# toiletino.net
KiCad netlist of a schematic drawn in EAGLE
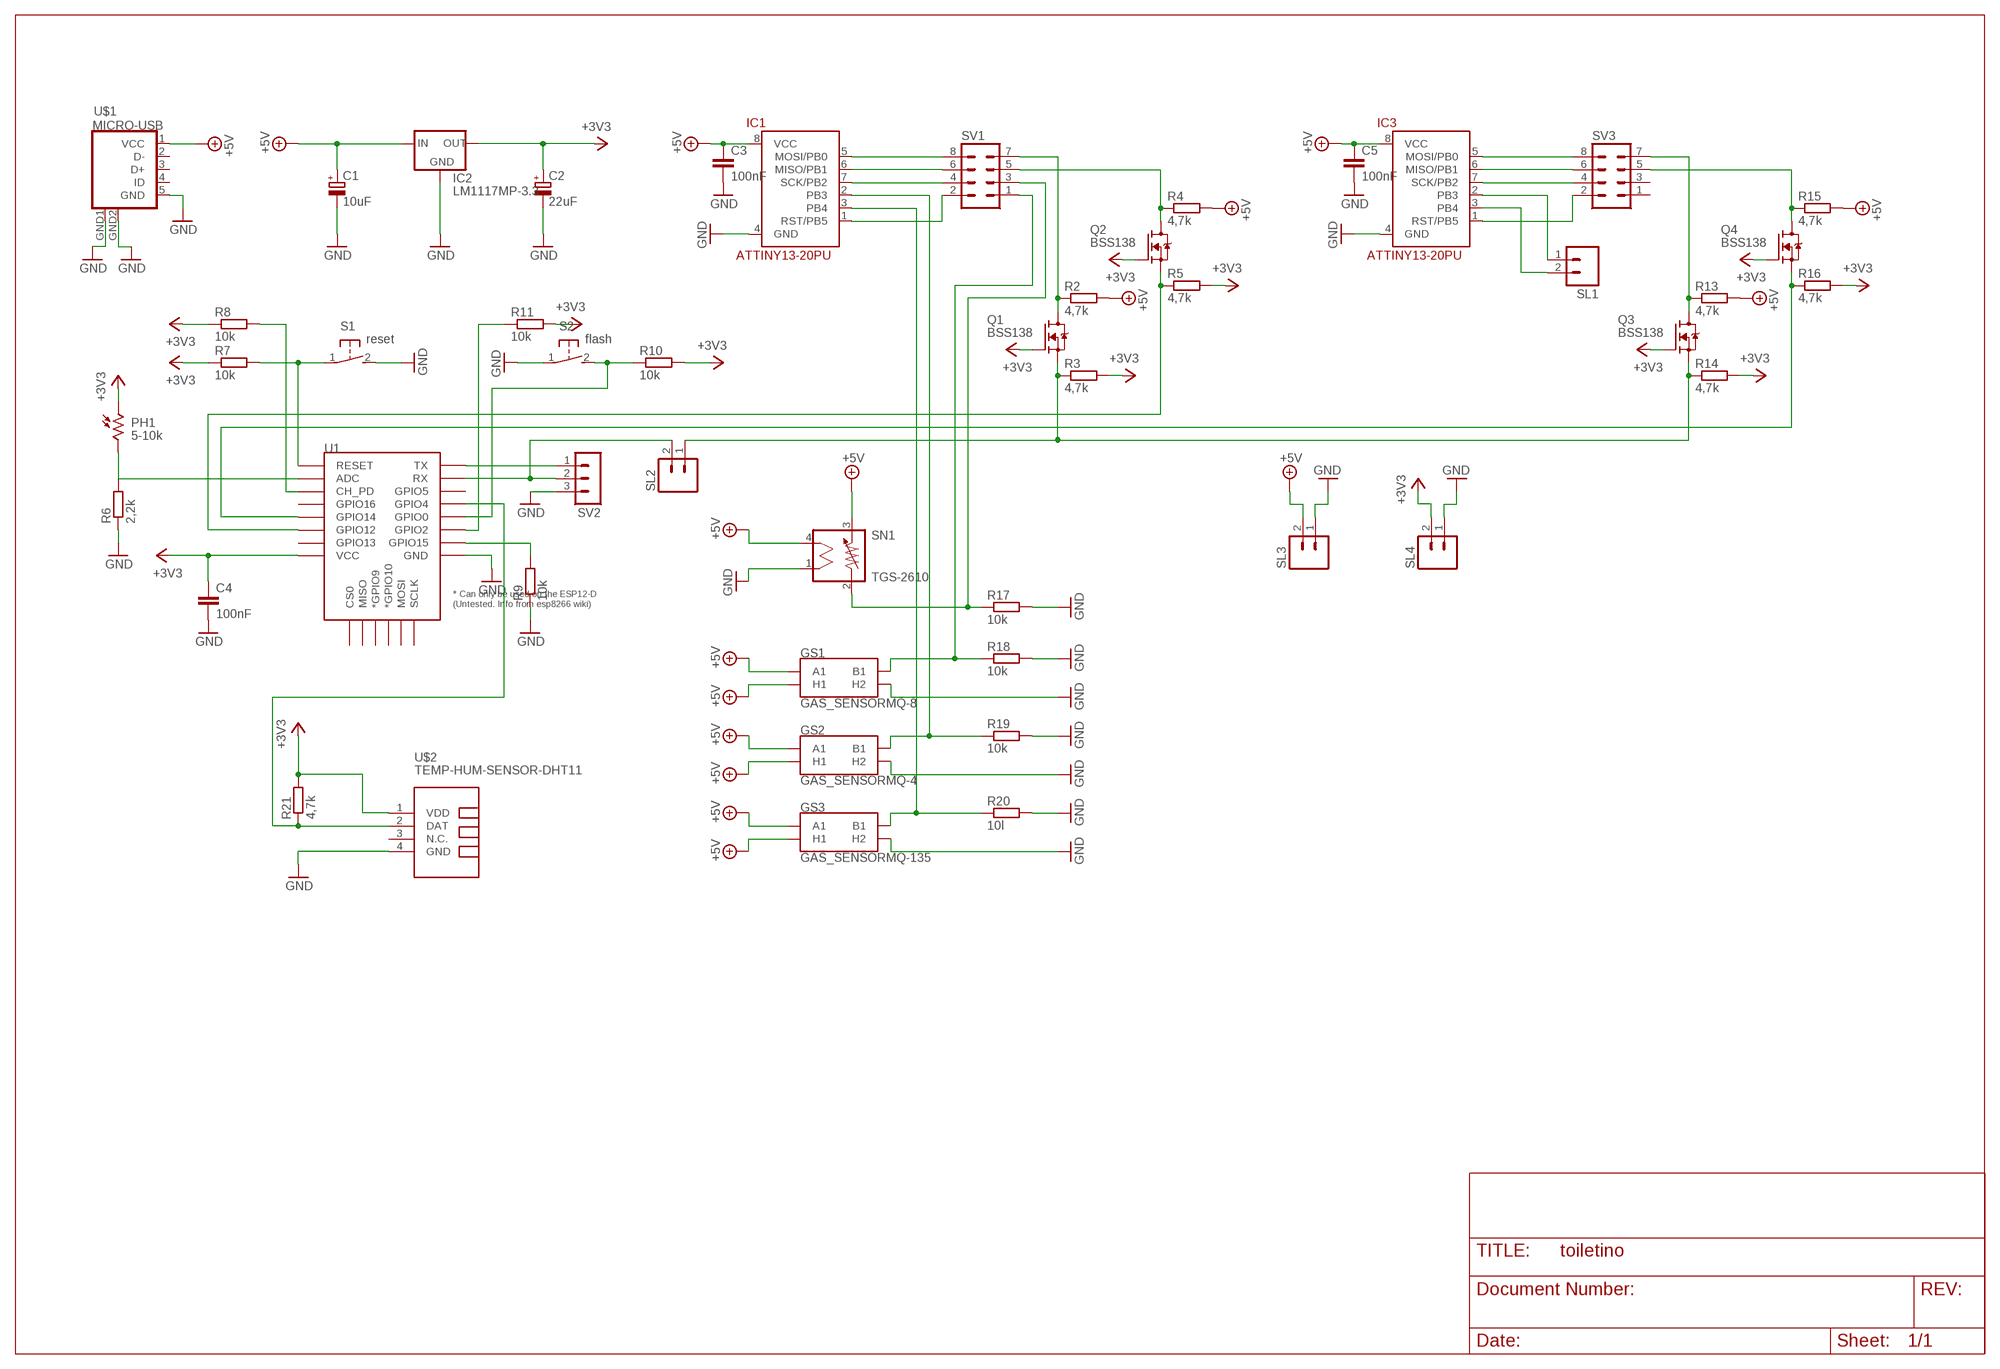
[diagram p0: schematic, sheet 1]

(export (version "E")
  (design (tool "Eeschema 10.0.6"))
  (components
    (comp (ref "C1")
      (value "10uF")
      (footprint "eagle-import:E2,5-6")
      (libsource (lib "eagle-import") (part "CPOL-EUE2.5-6"))
    )
    (comp (ref "C2")
      (value "22uF")
      (footprint "eagle-import:E2,5-6")
      (libsource (lib "eagle-import") (part "CPOL-EUE2.5-6"))
    )
    (comp (ref "C3")
      (value "100nF")
      (footprint "eagle-import:C025-025X050")
      (libsource (lib "eagle-import") (part "C-EU025-025X050"))
    )
    (comp (ref "C4")
      (value "100nF")
      (footprint "eagle-import:C025-025X050")
      (libsource (lib "eagle-import") (part "C-EU025-025X050"))
    )
    (comp (ref "C5")
      (value "100nF")
      (footprint "eagle-import:C025-025X050")
      (libsource (lib "eagle-import") (part "C-EU025-025X050"))
    )
    (comp (ref "GS1")
      (value "GAS_SENSORMQ-8")
      (footprint "eagle-import:GAS_SENSOR")
      (libsource (lib "eagle-import") (part "GAS_SENSORMQ-8"))
    )
    (comp (ref "GS2")
      (value "GAS_SENSORMQ-4")
      (footprint "eagle-import:GAS_SENSOR")
      (libsource (lib "eagle-import") (part "GAS_SENSORMQ-4"))
    )
    (comp (ref "GS3")
      (value "GAS_SENSORMQ-135")
      (footprint "eagle-import:GAS_SENSOR")
      (libsource (lib "eagle-import") (part "GAS_SENSORMQ-3"))
    )
    (comp (ref "IC1")
      (value "ATTINY13-20PU")
      (footprint "eagle-import:DIL08")
      (libsource (lib "eagle-import") (part "ATTINY13-20PU"))
    )
    (comp (ref "IC2")
      (value "LM1117MP-3.3")
      (footprint "eagle-import:SOT223")
      (fields (field (name "MF") "Texas Instruments"))
      (libsource (lib "eagle-import") (part "LM1117?-MP3.3"))
    )
    (comp (ref "IC3")
      (value "ATTINY13-20PU")
      (footprint "eagle-import:DIL08")
      (libsource (lib "eagle-import") (part "ATTINY13-20PU"))
    )
    (comp (ref "PH1")
      (value "5-10k")
      (footprint "eagle-import:TO-5_V10")
      (libsource (lib "eagle-import") (part "?1060V_21"))
    )
    (comp (ref "Q1")
      (value "BSS138")
      (footprint "eagle-import:SOT23")
      (fields (field (name "MF") "Fairchild"))
      (libsource (lib "eagle-import") (part "BSS138"))
    )
    (comp (ref "Q2")
      (value "BSS138")
      (footprint "eagle-import:SOT23")
      (fields (field (name "MF") "Fairchild"))
      (libsource (lib "eagle-import") (part "BSS138"))
    )
    (comp (ref "Q3")
      (value "BSS138")
      (footprint "eagle-import:SOT23")
      (fields (field (name "MF") "Fairchild"))
      (libsource (lib "eagle-import") (part "BSS138"))
    )
    (comp (ref "Q4")
      (value "BSS138")
      (footprint "eagle-import:SOT23")
      (fields (field (name "MF") "Fairchild"))
      (libsource (lib "eagle-import") (part "BSS138"))
    )
    (comp (ref "R2")
      (value "4,7k")
      (footprint "eagle-import:0207_10")
      (libsource (lib "eagle-import") (part "R-EU_0207/10"))
    )
    (comp (ref "R3")
      (value "4,7k")
      (footprint "eagle-import:0207_10")
      (libsource (lib "eagle-import") (part "R-EU_0207/10"))
    )
    (comp (ref "R4")
      (value "4,7k")
      (footprint "eagle-import:0207_10")
      (libsource (lib "eagle-import") (part "R-EU_0207/10"))
    )
    (comp (ref "R5")
      (value "4,7k")
      (footprint "eagle-import:0207_10")
      (libsource (lib "eagle-import") (part "R-EU_0207/10"))
    )
    (comp (ref "R6")
      (value "2,2k")
      (footprint "eagle-import:0207_10")
      (libsource (lib "eagle-import") (part "R-EU_0207/10"))
    )
    (comp (ref "R7")
      (value "10k")
      (footprint "eagle-import:0207_10")
      (libsource (lib "eagle-import") (part "R-EU_0207/10"))
    )
    (comp (ref "R8")
      (value "10k")
      (footprint "eagle-import:0207_10")
      (libsource (lib "eagle-import") (part "R-EU_0207/10"))
    )
    (comp (ref "R9")
      (value "10k")
      (footprint "eagle-import:0207_10")
      (libsource (lib "eagle-import") (part "R-EU_0207/10"))
    )
    (comp (ref "R10")
      (value "10k")
      (footprint "eagle-import:0207_10")
      (libsource (lib "eagle-import") (part "R-EU_0207/10"))
    )
    (comp (ref "R11")
      (value "10k")
      (footprint "eagle-import:0207_10")
      (libsource (lib "eagle-import") (part "R-EU_0207/10"))
    )
    (comp (ref "R13")
      (value "4,7k")
      (footprint "eagle-import:0207_10")
      (libsource (lib "eagle-import") (part "R-EU_0207/10"))
    )
    (comp (ref "R14")
      (value "4,7k")
      (footprint "eagle-import:0207_10")
      (libsource (lib "eagle-import") (part "R-EU_0207/10"))
    )
    (comp (ref "R15")
      (value "4,7k")
      (footprint "eagle-import:0207_10")
      (libsource (lib "eagle-import") (part "R-EU_0207/10"))
    )
    (comp (ref "R16")
      (value "4,7k")
      (footprint "eagle-import:0207_10")
      (libsource (lib "eagle-import") (part "R-EU_0207/10"))
    )
    (comp (ref "R17")
      (value "10k")
      (footprint "eagle-import:0207_10")
      (libsource (lib "eagle-import") (part "R-EU_0207/10"))
    )
    (comp (ref "R18")
      (value "10k")
      (footprint "eagle-import:0207_10")
      (libsource (lib "eagle-import") (part "R-EU_0207/10"))
    )
    (comp (ref "R19")
      (value "10k")
      (footprint "eagle-import:0207_10")
      (libsource (lib "eagle-import") (part "R-EU_0207/10"))
    )
    (comp (ref "R20")
      (value "10l")
      (footprint "eagle-import:0207_10")
      (libsource (lib "eagle-import") (part "R-EU_0207/10"))
    )
    (comp (ref "R21")
      (value "4,7k")
      (footprint "eagle-import:0207_10")
      (libsource (lib "eagle-import") (part "R-EU_0207/10"))
    )
    (comp (ref "S1")
      (value "reset")
      (footprint "eagle-import:DTS-3")
      (libsource (lib "eagle-import") (part "DTS-3"))
    )
    (comp (ref "S2")
      (value "flash")
      (footprint "eagle-import:DTS-3")
      (libsource (lib "eagle-import") (part "DTS-3"))
    )
    (comp (ref "SL1")
      (value "MA02")
      (footprint "eagle-import:02PA")
      (libsource (lib "eagle-import") (part "MA02"))
    )
    (comp (ref "SL2")
      (value "MA02")
      (footprint "eagle-import:02PA")
      (libsource (lib "eagle-import") (part "MA02"))
    )
    (comp (ref "SL3")
      (value "MA02")
      (footprint "eagle-import:02PA")
      (libsource (lib "eagle-import") (part "MA02"))
    )
    (comp (ref "SL4")
      (value "MA02")
      (footprint "eagle-import:02PA")
      (libsource (lib "eagle-import") (part "MA02"))
    )
    (comp (ref "SN1")
      (value "TGS-2610")
      (footprint "eagle-import:TGS-2610")
      (libsource (lib "eagle-import") (part "TGS-2610"))
    )
    (comp (ref "SV1")
      (value "MA04-2")
      (footprint "eagle-import:MA04-2")
      (libsource (lib "eagle-import") (part "MA04-2"))
    )
    (comp (ref "SV2")
      (value "MA03-1")
      (footprint "eagle-import:MA03-1")
      (libsource (lib "eagle-import") (part "MA03-1"))
    )
    (comp (ref "SV3")
      (value "MA04-2")
      (footprint "eagle-import:MA04-2")
      (libsource (lib "eagle-import") (part "MA04-2"))
    )
    (comp (ref "U$1")
      (value "MICRO-USB")
      (footprint "eagle-import:MICRO-USB")
      (libsource (lib "eagle-import") (part "MICRO-USB"))
    )
    (comp (ref "U$2")
      (value "TEMP-HUM-SENSOR-DHT11")
      (footprint "eagle-import:TEMP-HUM-SENSOR-DHT11")
      (libsource (lib "eagle-import") (part "TEMP-HUM-SENSOR-DHT11"))
    )
    (comp (ref "U1")
      (value "ESP12ESMD")
      (footprint "eagle-import:ESP12E-SMD")
      (libsource (lib "eagle-import") (part "ESP12ESMD"))
    )
  )
  (nets
    (net (code "1") (name "+3V3") (class "Default")
      (node (ref "C2") (pin "+") (pinfunction "+_+") (pintype "passive"))
      (node (ref "C4") (pin "1") (pinfunction "1_1") (pintype "passive"))
      (node (ref "IC2") (pin "2") (pinfunction "OUT_2") (pintype "passive"))
      (node (ref "IC2") (pin "4") (pinfunction "OUT_4") (pintype "passive"))
      (node (ref "PH1") (pin "1") (pinfunction "1_1") (pintype "passive"))
      (node (ref "Q1") (pin "1") (pinfunction "G_1") (pintype "passive"))
      (node (ref "Q2") (pin "1") (pinfunction "G_1") (pintype "passive"))
      (node (ref "Q3") (pin "1") (pinfunction "G_1") (pintype "passive"))
      (node (ref "Q4") (pin "1") (pinfunction "G_1") (pintype "passive"))
      (node (ref "R10") (pin "2") (pinfunction "2_2") (pintype "passive"))
      (node (ref "R11") (pin "2") (pinfunction "2_2") (pintype "passive"))
      (node (ref "R14") (pin "2") (pinfunction "2_2") (pintype "passive"))
      (node (ref "R16") (pin "2") (pinfunction "2_2") (pintype "passive"))
      (node (ref "R21") (pin "2") (pinfunction "2_2") (pintype "passive"))
      (node (ref "R3") (pin "2") (pinfunction "2_2") (pintype "passive"))
      (node (ref "R5") (pin "2") (pinfunction "2_2") (pintype "passive"))
      (node (ref "R7") (pin "1") (pinfunction "1_1") (pintype "passive"))
      (node (ref "R8") (pin "1") (pinfunction "1_1") (pintype "passive"))
      (node (ref "SL4") (pin "2") (pinfunction "2_2") (pintype "passive"))
      (node (ref "U$2") (pin "1") (pinfunction "VDD_1") (pintype "power_in"))
      (node (ref "U1") (pin "VCC") (pinfunction "VCC_VCC") (pintype "bidirectional"))
    )
    (net (code "2") (name "+5V") (class "Default")
      (node (ref "C1") (pin "+") (pinfunction "+_+") (pintype "passive"))
      (node (ref "C3") (pin "1") (pinfunction "1_1") (pintype "passive"))
      (node (ref "C5") (pin "1") (pinfunction "1_1") (pintype "passive"))
      (node (ref "GS1") (pin "A1") (pinfunction "A1_A1") (pintype "bidirectional"))
      (node (ref "GS1") (pin "A2") (pinfunction "A1_A2") (pintype "bidirectional"))
      (node (ref "GS1") (pin "HA") (pinfunction "H1_HA") (pintype "bidirectional"))
      (node (ref "GS2") (pin "A1") (pinfunction "A1_A1") (pintype "bidirectional"))
      (node (ref "GS2") (pin "A2") (pinfunction "A1_A2") (pintype "bidirectional"))
      (node (ref "GS2") (pin "HA") (pinfunction "H1_HA") (pintype "bidirectional"))
      (node (ref "GS3") (pin "A1") (pinfunction "A1_A1") (pintype "bidirectional"))
      (node (ref "GS3") (pin "A2") (pinfunction "A1_A2") (pintype "bidirectional"))
      (node (ref "GS3") (pin "HA") (pinfunction "H1_HA") (pintype "bidirectional"))
      (node (ref "IC1") (pin "8") (pinfunction "VCC_8") (pintype "power_in"))
      (node (ref "IC2") (pin "3") (pinfunction "IN_3") (pintype "input"))
      (node (ref "IC3") (pin "8") (pinfunction "VCC_8") (pintype "power_in"))
      (node (ref "R13") (pin "2") (pinfunction "2_2") (pintype "passive"))
      (node (ref "R15") (pin "2") (pinfunction "2_2") (pintype "passive"))
      (node (ref "R2") (pin "2") (pinfunction "2_2") (pintype "passive"))
      (node (ref "R4") (pin "2") (pinfunction "2_2") (pintype "passive"))
      (node (ref "SL3") (pin "2") (pinfunction "2_2") (pintype "passive"))
      (node (ref "SN1") (pin "3") (pinfunction "3_3") (pintype "passive"))
      (node (ref "SN1") (pin "4") (pinfunction "4_4") (pintype "passive"))
      (node (ref "U$1") (pin "1") (pinfunction "VCC_1") (pintype "power_in"))
    )
    (net (code "3") (name "GND") (class "Default")
      (node (ref "C1") (pin "-") (pinfunction "-_-") (pintype "passive"))
      (node (ref "C2") (pin "-") (pinfunction "-_-") (pintype "passive"))
      (node (ref "C3") (pin "2") (pinfunction "2_2") (pintype "passive"))
      (node (ref "C4") (pin "2") (pinfunction "2_2") (pintype "passive"))
      (node (ref "C5") (pin "2") (pinfunction "2_2") (pintype "passive"))
      (node (ref "GS1") (pin "HB") (pinfunction "H2_HB") (pintype "bidirectional"))
      (node (ref "GS2") (pin "HB") (pinfunction "H2_HB") (pintype "bidirectional"))
      (node (ref "GS3") (pin "HB") (pinfunction "H2_HB") (pintype "bidirectional"))
      (node (ref "IC1") (pin "4") (pinfunction "GND_4") (pintype "power_in"))
      (node (ref "IC2") (pin "1") (pinfunction "GND_1") (pintype "input"))
      (node (ref "IC3") (pin "4") (pinfunction "GND_4") (pintype "power_in"))
      (node (ref "R17") (pin "2") (pinfunction "2_2") (pintype "passive"))
      (node (ref "R18") (pin "2") (pinfunction "2_2") (pintype "passive"))
      (node (ref "R19") (pin "2") (pinfunction "2_2") (pintype "passive"))
      (node (ref "R20") (pin "2") (pinfunction "2_2") (pintype "passive"))
      (node (ref "R6") (pin "1") (pinfunction "1_1") (pintype "passive"))
      (node (ref "R9") (pin "1") (pinfunction "1_1") (pintype "passive"))
      (node (ref "S1") (pin "2") (pinfunction "2_2") (pintype "passive"))
      (node (ref "S2") (pin "1") (pinfunction "1_1") (pintype "passive"))
      (node (ref "SL3") (pin "1") (pinfunction "1_1") (pintype "passive"))
      (node (ref "SL4") (pin "1") (pinfunction "1_1") (pintype "passive"))
      (node (ref "SN1") (pin "1") (pinfunction "1_1") (pintype "passive"))
      (node (ref "SV2") (pin "3") (pinfunction "3_3") (pintype "passive"))
      (node (ref "U$1") (pin "5") (pinfunction "GND_5") (pintype "power_in"))
      (node (ref "U$1") (pin "GND1") (pinfunction "GND_GND1") (pintype "power_in"))
      (node (ref "U$1") (pin "GND2") (pinfunction "GND_GND2") (pintype "power_in"))
      (node (ref "U$2") (pin "4") (pinfunction "GND_4") (pintype "power_in"))
      (node (ref "U1") (pin "GND") (pinfunction "GND_GND") (pintype "bidirectional"))
    )
    (net (code "4") (name "Net-(GS1-B1-PadB2)") (class "Default")
      (node (ref "GS1") (pin "B1") (pinfunction "B1_B1") (pintype "bidirectional"))
      (node (ref "GS1") (pin "B2") (pinfunction "B1_B2") (pintype "bidirectional"))
      (node (ref "R18") (pin "1") (pinfunction "1_1") (pintype "passive"))
      (node (ref "SV1") (pin "1") (pinfunction "1_1") (pintype "passive"))
    )
    (net (code "5") (name "Net-(IC1-MISO{slash}PB1)") (class "Default")
      (node (ref "IC1") (pin "6") (pinfunction "MISO/PB1_6") (pintype "bidirectional"))
      (node (ref "SV1") (pin "6") (pinfunction "6_6") (pintype "passive"))
    )
    (net (code "6") (name "Net-(IC1-MOSI{slash}PB0)") (class "Default")
      (node (ref "IC1") (pin "5") (pinfunction "MOSI/PB0_5") (pintype "bidirectional"))
      (node (ref "SV1") (pin "8") (pinfunction "8_8") (pintype "passive"))
    )
    (net (code "7") (name "Net-(IC1-PB3)") (class "Default")
      (node (ref "GS2") (pin "B1") (pinfunction "B1_B1") (pintype "bidirectional"))
      (node (ref "GS2") (pin "B2") (pinfunction "B1_B2") (pintype "bidirectional"))
      (node (ref "IC1") (pin "2") (pinfunction "PB3_2") (pintype "bidirectional"))
      (node (ref "R19") (pin "1") (pinfunction "1_1") (pintype "passive"))
    )
    (net (code "8") (name "Net-(IC1-PB4)") (class "Default")
      (node (ref "GS3") (pin "B1") (pinfunction "B1_B1") (pintype "bidirectional"))
      (node (ref "GS3") (pin "B2") (pinfunction "B1_B2") (pintype "bidirectional"))
      (node (ref "IC1") (pin "3") (pinfunction "PB4_3") (pintype "bidirectional"))
      (node (ref "R20") (pin "1") (pinfunction "1_1") (pintype "passive"))
    )
    (net (code "9") (name "Net-(IC1-RST{slash}PB5)") (class "Default")
      (node (ref "IC1") (pin "1") (pinfunction "RST/PB5_1") (pintype "bidirectional"))
      (node (ref "SV1") (pin "2") (pinfunction "2_2") (pintype "passive"))
    )
    (net (code "10") (name "Net-(IC1-SCK{slash}PB2)") (class "Default")
      (node (ref "IC1") (pin "7") (pinfunction "SCK/PB2_7") (pintype "bidirectional"))
      (node (ref "SV1") (pin "4") (pinfunction "4_4") (pintype "passive"))
    )
    (net (code "11") (name "Net-(IC3-MISO{slash}PB1)") (class "Default")
      (node (ref "IC3") (pin "6") (pinfunction "MISO/PB1_6") (pintype "bidirectional"))
      (node (ref "SV3") (pin "6") (pinfunction "6_6") (pintype "passive"))
    )
    (net (code "12") (name "Net-(IC3-MOSI{slash}PB0)") (class "Default")
      (node (ref "IC3") (pin "5") (pinfunction "MOSI/PB0_5") (pintype "bidirectional"))
      (node (ref "SV3") (pin "8") (pinfunction "8_8") (pintype "passive"))
    )
    (net (code "13") (name "Net-(IC3-PB3)") (class "Default")
      (node (ref "IC3") (pin "2") (pinfunction "PB3_2") (pintype "bidirectional"))
      (node (ref "SL1") (pin "1") (pinfunction "1_1") (pintype "passive"))
    )
    (net (code "14") (name "Net-(IC3-PB4)") (class "Default")
      (node (ref "IC3") (pin "3") (pinfunction "PB4_3") (pintype "bidirectional"))
      (node (ref "SL1") (pin "2") (pinfunction "2_2") (pintype "passive"))
    )
    (net (code "15") (name "Net-(IC3-RST{slash}PB5)") (class "Default")
      (node (ref "IC3") (pin "1") (pinfunction "RST/PB5_1") (pintype "bidirectional"))
      (node (ref "SV3") (pin "2") (pinfunction "2_2") (pintype "passive"))
    )
    (net (code "16") (name "Net-(IC3-SCK{slash}PB2)") (class "Default")
      (node (ref "IC3") (pin "7") (pinfunction "SCK/PB2_7") (pintype "bidirectional"))
      (node (ref "SV3") (pin "4") (pinfunction "4_4") (pintype "passive"))
    )
    (net (code "17") (name "Net-(PH1-Pad2)") (class "Default")
      (node (ref "PH1") (pin "2") (pinfunction "2_2") (pintype "passive"))
      (node (ref "R6") (pin "2") (pinfunction "2_2") (pintype "passive"))
      (node (ref "U1") (pin "ADC") (pinfunction "ADC_ADC") (pintype "bidirectional"))
    )
    (net (code "18") (name "Net-(Q1-D)") (class "Default")
      (node (ref "Q1") (pin "3") (pinfunction "D_3") (pintype "passive"))
      (node (ref "R2") (pin "1") (pinfunction "1_1") (pintype "passive"))
      (node (ref "SV1") (pin "7") (pinfunction "7_7") (pintype "passive"))
    )
    (net (code "19") (name "Net-(Q1-S)") (class "Default")
      (node (ref "Q1") (pin "2") (pinfunction "S_2") (pintype "passive"))
      (node (ref "Q3") (pin "2") (pinfunction "S_2") (pintype "passive"))
      (node (ref "R14") (pin "1") (pinfunction "1_1") (pintype "passive"))
      (node (ref "R3") (pin "1") (pinfunction "1_1") (pintype "passive"))
      (node (ref "SL2") (pin "1") (pinfunction "1_1") (pintype "passive"))
    )
    (net (code "20") (name "Net-(Q2-D)") (class "Default")
      (node (ref "Q2") (pin "3") (pinfunction "D_3") (pintype "passive"))
      (node (ref "R4") (pin "1") (pinfunction "1_1") (pintype "passive"))
      (node (ref "SV1") (pin "5") (pinfunction "5_5") (pintype "passive"))
    )
    (net (code "21") (name "Net-(Q2-S)") (class "Default")
      (node (ref "Q2") (pin "2") (pinfunction "S_2") (pintype "passive"))
      (node (ref "R5") (pin "1") (pinfunction "1_1") (pintype "passive"))
      (node (ref "U1") (pin "GPIO12") (pinfunction "GPIO12_GPIO12") (pintype "bidirectional"))
    )
    (net (code "22") (name "Net-(Q3-D)") (class "Default")
      (node (ref "Q3") (pin "3") (pinfunction "D_3") (pintype "passive"))
      (node (ref "R13") (pin "1") (pinfunction "1_1") (pintype "passive"))
      (node (ref "SV3") (pin "7") (pinfunction "7_7") (pintype "passive"))
    )
    (net (code "23") (name "Net-(Q4-D)") (class "Default")
      (node (ref "Q4") (pin "3") (pinfunction "D_3") (pintype "passive"))
      (node (ref "R15") (pin "1") (pinfunction "1_1") (pintype "passive"))
      (node (ref "SV3") (pin "5") (pinfunction "5_5") (pintype "passive"))
    )
    (net (code "24") (name "Net-(Q4-S)") (class "Default")
      (node (ref "Q4") (pin "2") (pinfunction "S_2") (pintype "passive"))
      (node (ref "R16") (pin "1") (pinfunction "1_1") (pintype "passive"))
      (node (ref "U1") (pin "GPIO14") (pinfunction "GPIO14_GPIO14") (pintype "bidirectional"))
    )
    (net (code "25") (name "Net-(R7-Pad2)") (class "Default")
      (node (ref "R7") (pin "2") (pinfunction "2_2") (pintype "passive"))
      (node (ref "S1") (pin "1") (pinfunction "1_1") (pintype "passive"))
      (node (ref "U1") (pin "RESET") (pinfunction "RESET_RESET") (pintype "bidirectional"))
    )
    (net (code "26") (name "Net-(R8-Pad2)") (class "Default")
      (node (ref "R8") (pin "2") (pinfunction "2_2") (pintype "passive"))
      (node (ref "U1") (pin "CH_PD") (pinfunction "CH_PD_CH_PD") (pintype "bidirectional"))
    )
    (net (code "27") (name "Net-(R9-Pad2)") (class "Default")
      (node (ref "R9") (pin "2") (pinfunction "2_2") (pintype "passive"))
      (node (ref "U1") (pin "GPIO15") (pinfunction "GPIO15_GPIO15") (pintype "bidirectional"))
    )
    (net (code "28") (name "Net-(R10-Pad1)") (class "Default")
      (node (ref "R10") (pin "1") (pinfunction "1_1") (pintype "passive"))
      (node (ref "S2") (pin "2") (pinfunction "2_2") (pintype "passive"))
      (node (ref "U1") (pin "GPIO0") (pinfunction "GPIO0_GPIO0") (pintype "bidirectional"))
    )
    (net (code "29") (name "Net-(R11-Pad1)") (class "Default")
      (node (ref "R11") (pin "1") (pinfunction "1_1") (pintype "passive"))
      (node (ref "U1") (pin "GPIO2") (pinfunction "GPIO2_GPIO2") (pintype "bidirectional"))
    )
    (net (code "30") (name "Net-(R17-Pad1)") (class "Default")
      (node (ref "R17") (pin "1") (pinfunction "1_1") (pintype "passive"))
      (node (ref "SN1") (pin "2") (pinfunction "2_2") (pintype "passive"))
      (node (ref "SV1") (pin "3") (pinfunction "3_3") (pintype "passive"))
    )
    (net (code "31") (name "Net-(U$2-DAT)") (class "Default")
      (node (ref "R21") (pin "1") (pinfunction "1_1") (pintype "passive"))
      (node (ref "U$2") (pin "2") (pinfunction "DAT_2") (pintype "bidirectional"))
      (node (ref "U1") (pin "GPIO4") (pinfunction "GPIO4_GPIO4") (pintype "bidirectional"))
    )
    (net (code "32") (name "Net-(U1-RX)") (class "Default")
      (node (ref "SL2") (pin "2") (pinfunction "2_2") (pintype "passive"))
      (node (ref "SV2") (pin "2") (pinfunction "2_2") (pintype "passive"))
      (node (ref "U1") (pin "RXD0") (pinfunction "RX_RXD0") (pintype "bidirectional"))
    )
    (net (code "33") (name "Net-(U1-TX)") (class "Default")
      (node (ref "SV2") (pin "1") (pinfunction "1_1") (pintype "passive"))
      (node (ref "U1") (pin "TXD0") (pinfunction "TX_TXD0") (pintype "bidirectional"))
    )
    (net (code "34") (name "unconnected-(SV3-Pad1)") (class "Default")
      (node (ref "SV3") (pin "1") (pinfunction "1_1") (pintype "passive"))
    )
    (net (code "35") (name "unconnected-(SV3-Pad3)") (class "Default")
      (node (ref "SV3") (pin "3") (pinfunction "3_3") (pintype "passive"))
    )
    (net (code "36") (name "unconnected-(U$1-D+-Pad3)") (class "Default")
      (node (ref "U$1") (pin "3") (pinfunction "D+_3") (pintype "bidirectional"))
    )
    (net (code "37") (name "unconnected-(U$1-D--Pad2)") (class "Default")
      (node (ref "U$1") (pin "2") (pinfunction "D-_2") (pintype "bidirectional"))
    )
    (net (code "38") (name "unconnected-(U$1-ID-Pad4)") (class "Default")
      (node (ref "U$1") (pin "4") (pinfunction "ID_4") (pintype "bidirectional"))
    )
    (net (code "39") (name "unconnected-(U$2-N.C.-Pad3)") (class "Default")
      (node (ref "U$2") (pin "3") (pinfunction "N.C._3") (pintype "passive"))
    )
    (net (code "40") (name "unconnected-(U1-*GPIO9-PadGPIO9)") (class "Default")
      (node (ref "U1") (pin "GPIO9") (pinfunction "*GPIO9_GPIO9") (pintype "bidirectional"))
    )
    (net (code "41") (name "unconnected-(U1-*GPIO10-PadGPIO10)") (class "Default")
      (node (ref "U1") (pin "GPIO10") (pinfunction "*GPIO10_GPIO10") (pintype "bidirectional"))
    )
    (net (code "42") (name "unconnected-(U1-PadCS0)") (class "Default")
      (node (ref "U1") (pin "CS0") (pinfunction "CS0_CS0") (pintype "bidirectional"))
    )
    (net (code "43") (name "unconnected-(U1-PadGPIO5)") (class "Default")
      (node (ref "U1") (pin "GPIO5") (pinfunction "GPIO5_GPIO5") (pintype "bidirectional"))
    )
    (net (code "44") (name "unconnected-(U1-PadGPIO13)") (class "Default")
      (node (ref "U1") (pin "GPIO13") (pinfunction "GPIO13_GPIO13") (pintype "bidirectional"))
    )
    (net (code "45") (name "unconnected-(U1-PadGPIO16)") (class "Default")
      (node (ref "U1") (pin "GPIO16") (pinfunction "GPIO16_GPIO16") (pintype "bidirectional"))
    )
    (net (code "46") (name "unconnected-(U1-PadMISO)") (class "Default")
      (node (ref "U1") (pin "MISO") (pinfunction "MISO_MISO") (pintype "bidirectional"))
    )
    (net (code "47") (name "unconnected-(U1-PadMOSI)") (class "Default")
      (node (ref "U1") (pin "MOSI") (pinfunction "MOSI_MOSI") (pintype "bidirectional"))
    )
    (net (code "48") (name "unconnected-(U1-PadSCLK)") (class "Default")
      (node (ref "U1") (pin "SCLK") (pinfunction "SCLK_SCLK") (pintype "bidirectional"))
    )
  )
)
